# Sheet1.net
KiCad netlist of a schematic drawn in Altium Designer
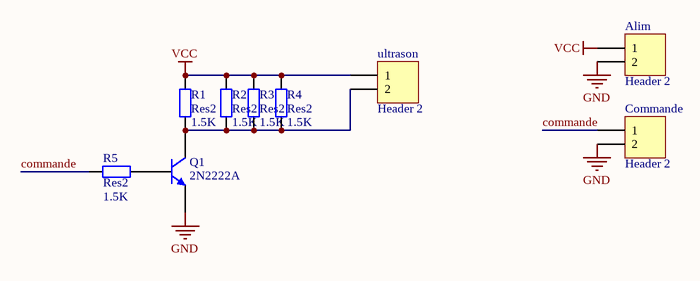
[diagram p0: Sheet1.SchDoc]

(export (version "E")
  (design (tool "Eeschema 10.0.6"))
  (components
    (comp (ref "Alim")
      (value "Header 2")
      (footprint "HDR1X2")
      (description "Header, 2-Pin")
      (fields (field (name "PUBLISHER") "Altium Limited"))
      (libsource (lib "Miscellaneous Connectors") (part "Header 2"))
    )
    (comp (ref "Commande")
      (value "Header 2")
      (footprint "HDR1X2")
      (description "Header, 2-Pin")
      (fields (field (name "PUBLISHER") "Altium Limited"))
      (libsource (lib "Miscellaneous Connectors") (part "Header 2"))
    )
    (comp (ref "Q1")
      (value "2N2222A")
      (footprint "TO-18")
      (description "High Speed Switches")
      (fields (field (name "PUBLISHER") "Altium Limited"))
      (libsource (lib "LIBRAIRIE_INTEGREE_PHELMA1") (part "2N2222A"))
    )
    (comp (ref "R1")
      (value "Res2")
      (footprint "AXIAL-0.4")
      (description "Resistor")
      (fields (field (name "ALTIUM_VALUE") "1.5K") (field (name "PUBLISHER") "Altium Limited"))
      (libsource (lib "Miscellaneous Devices") (part "Res2"))
    )
    (comp (ref "R2")
      (value "Res2")
      (footprint "AXIAL-0.4")
      (description "Resistor")
      (fields (field (name "ALTIUM_VALUE") "1.5K") (field (name "PUBLISHER") "Altium Limited"))
      (libsource (lib "Miscellaneous Devices") (part "Res2"))
    )
    (comp (ref "R3")
      (value "Res2")
      (footprint "AXIAL-0.4")
      (description "Resistor")
      (fields (field (name "ALTIUM_VALUE") "1.5K") (field (name "PUBLISHER") "Altium Limited"))
      (libsource (lib "Miscellaneous Devices") (part "Res2"))
    )
    (comp (ref "R4")
      (value "Res2")
      (footprint "AXIAL-0.4")
      (description "Resistor")
      (fields (field (name "ALTIUM_VALUE") "1.5K") (field (name "PUBLISHER") "Altium Limited"))
      (libsource (lib "Miscellaneous Devices") (part "Res2"))
    )
    (comp (ref "R5")
      (value "Res2")
      (footprint "AXIAL-0.4")
      (description "Resistor")
      (fields (field (name "ALTIUM_VALUE") "1.5K") (field (name "PUBLISHER") "Altium Limited"))
      (libsource (lib "") (part "Res2_1"))
    )
    (comp (ref "ultrason")
      (value "Header 2")
      (footprint "HDR1X2")
      (description "Header, 2-Pin")
      (fields (field (name "PUBLISHER") "Altium Limited"))
      (libsource (lib "Miscellaneous Connectors") (part "Header 2"))
    )
  )
  (nets
    (net (code "1") (name "/commande") (class "Default")
      (node (ref "Commande") (pin "1") (pinfunction "1_1") (pintype "passive"))
      (node (ref "R5") (pin "2") (pinfunction "2_2") (pintype "passive"))
    )
    (net (code "2") (name "GND") (class "Default")
      (node (ref "Alim") (pin "2") (pinfunction "2_2") (pintype "passive"))
      (node (ref "Commande") (pin "2") (pinfunction "2_2") (pintype "passive"))
      (node (ref "Q1") (pin "3") (pinfunction "E_3") (pintype "passive"))
    )
    (net (code "3") (name "Net-(Q1-B)") (class "Default")
      (node (ref "Q1") (pin "1") (pinfunction "B_1") (pintype "passive"))
      (node (ref "R5") (pin "1") (pinfunction "1_1") (pintype "passive"))
    )
    (net (code "4") (name "Net-(Q1-C)") (class "Default")
      (node (ref "Q1") (pin "2") (pinfunction "C_2") (pintype "passive"))
      (node (ref "R1") (pin "1") (pinfunction "1_1") (pintype "passive"))
      (node (ref "R2") (pin "1") (pinfunction "1_1") (pintype "passive"))
      (node (ref "R3") (pin "1") (pinfunction "1_1") (pintype "passive"))
      (node (ref "R4") (pin "1") (pinfunction "1_1") (pintype "passive"))
      (node (ref "ultrason") (pin "2") (pinfunction "2_2") (pintype "passive"))
    )
    (net (code "5") (name "VCC") (class "Default")
      (node (ref "Alim") (pin "1") (pinfunction "1_1") (pintype "passive"))
      (node (ref "R1") (pin "2") (pinfunction "2_2") (pintype "passive"))
      (node (ref "R2") (pin "2") (pinfunction "2_2") (pintype "passive"))
      (node (ref "R3") (pin "2") (pinfunction "2_2") (pintype "passive"))
      (node (ref "R4") (pin "2") (pinfunction "2_2") (pintype "passive"))
      (node (ref "ultrason") (pin "1") (pinfunction "1_1") (pintype "passive"))
    )
  )
)
